# CapacitiveSensorBreakout-v1_0.net
KiCad netlist of a schematic drawn in EAGLE
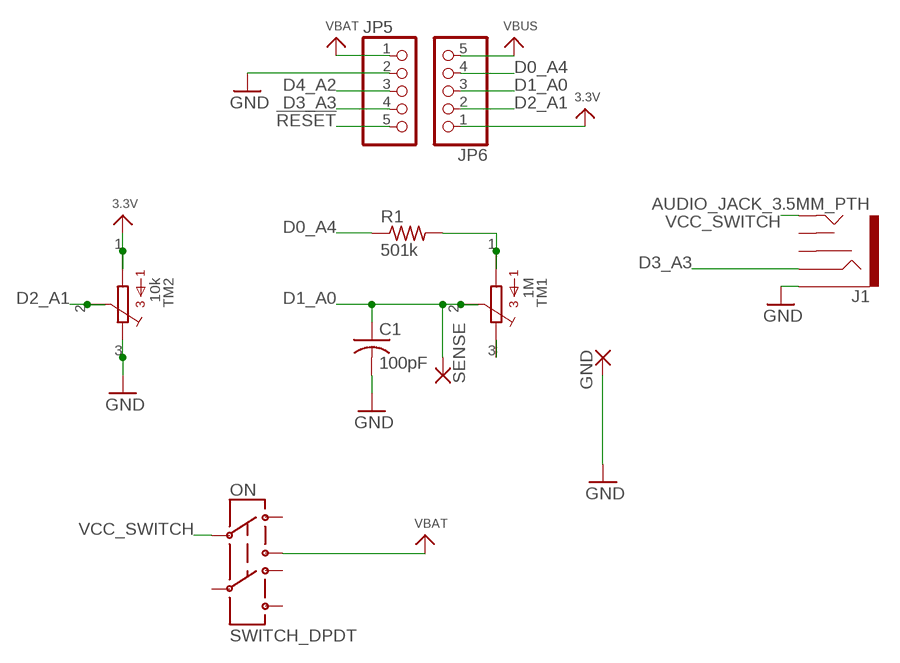
[diagram p0: schematic, sheet 1]

(export (version "E")
  (design (tool "Eeschema 10.0.6"))
  (components
    (comp (ref "C1")
      (value "100pF")
      (footprint "eagle-import:C0603")
      (libsource (lib "eagle-import") (part "C-USC0603"))
    )
    (comp (ref "GND")
      (value "1,6/0,8")
      (footprint "eagle-import:1,6_0,8")
      (libsource (lib "eagle-import") (part "1,6/0,8"))
    )
    (comp (ref "J1")
      (value "AUDIO_JACK_3.5MM_PTH")
      (footprint "eagle-import:AUDIO-JACK")
      (libsource (lib "eagle-import") (part "AUDIO_JACK_3.5MM_PTH"))
    )
    (comp (ref "JP5")
      (value "HEADER-1X576MIL")
      (footprint "eagle-import:1X05_ROUND_76")
      (libsource (lib "eagle-import") (part "HEADER-1X576MIL"))
    )
    (comp (ref "JP6")
      (value "HEADER-1X576MIL")
      (footprint "eagle-import:1X05_ROUND_76")
      (libsource (lib "eagle-import") (part "HEADER-1X576MIL"))
    )
    (comp (ref "ON")
      (value "SWITCH_DPDT")
      (footprint "eagle-import:JS_DPDT_TH")
      (libsource (lib "eagle-import") (part "SWITCH_DPDT"))
    )
    (comp (ref "R1")
      (value "501k")
      (footprint "eagle-import:R0603")
      (libsource (lib "eagle-import") (part "R-US_R0603"))
    )
    (comp (ref "SENSE")
      (value "1,6/0,8")
      (footprint "eagle-import:1,6_0,8")
      (libsource (lib "eagle-import") (part "1,6/0,8"))
    )
    (comp (ref "TM1")
      (value "1M")
      (footprint "eagle-import:3386-MULTI")
      (libsource (lib "eagle-import") (part "3386"))
    )
    (comp (ref "TM2")
      (value "10k")
      (footprint "eagle-import:3386-MULTI")
      (libsource (lib "eagle-import") (part "3386"))
    )
  )
  (nets
    (net (code "1") (name "/D0_A4") (class "Default")
      (node (ref "JP6") (pin "4") (pinfunction "4_4") (pintype "passive"))
      (node (ref "R1") (pin "1") (pinfunction "1_1") (pintype "passive"))
    )
    (net (code "2") (name "/D1_A0") (class "Default")
      (node (ref "C1") (pin "1") (pinfunction "1_1") (pintype "passive"))
      (node (ref "JP6") (pin "3") (pinfunction "3_3") (pintype "passive"))
      (node (ref "SENSE") (pin "1") (pinfunction "P_1") (pintype "passive"))
      (node (ref "TM1") (pin "2") (pinfunction "2_2") (pintype "passive"))
      (node (ref "TM1") (pin "5") (pinfunction "5_5") (pintype "passive"))
    )
    (net (code "3") (name "/D2_A1") (class "Default")
      (node (ref "JP6") (pin "2") (pinfunction "2_2") (pintype "passive"))
      (node (ref "TM2") (pin "2") (pinfunction "2_2") (pintype "passive"))
      (node (ref "TM2") (pin "5") (pinfunction "5_5") (pintype "passive"))
    )
    (net (code "4") (name "/D3_A3") (class "Default")
      (node (ref "J1") (pin "RING") (pinfunction "RING_RING") (pintype "bidirectional"))
      (node (ref "JP5") (pin "4") (pinfunction "4_4") (pintype "passive"))
    )
    (net (code "5") (name "/D4_A2") (class "Default")
      (node (ref "JP5") (pin "3") (pinfunction "3_3") (pintype "passive"))
    )
    (net (code "6") (name "/VCC_SWITCH") (class "Default")
      (node (ref "J1") (pin "TIP") (pinfunction "TIP_TIP") (pintype "bidirectional"))
      (node (ref "ON") (pin "2") (pinfunction "2_2") (pintype "bidirectional"))
    )
    (net (code "7") (name "/~{RESET}") (class "Default")
      (node (ref "JP5") (pin "5") (pinfunction "5_5") (pintype "passive"))
    )
    (net (code "8") (name "3.3V") (class "Default")
      (node (ref "JP6") (pin "1") (pinfunction "1_1") (pintype "passive"))
      (node (ref "TM2") (pin "1") (pinfunction "1_1") (pintype "passive"))
      (node (ref "TM2") (pin "4") (pinfunction "4_4") (pintype "passive"))
    )
    (net (code "9") (name "GND") (class "Default")
      (node (ref "C1") (pin "2") (pinfunction "2_2") (pintype "passive"))
      (node (ref "GND") (pin "1") (pinfunction "P_1") (pintype "passive"))
      (node (ref "J1") (pin "SLEEVE") (pinfunction "SLEEVE_SLEEVE") (pintype "bidirectional"))
      (node (ref "JP5") (pin "2") (pinfunction "2_2") (pintype "passive"))
      (node (ref "TM2") (pin "3") (pinfunction "3_3") (pintype "passive"))
      (node (ref "TM2") (pin "6") (pinfunction "6_6") (pintype "passive"))
    )
    (net (code "10") (name "Net-(R1-Pad2)") (class "Default")
      (node (ref "R1") (pin "2") (pinfunction "2_2") (pintype "passive"))
      (node (ref "TM1") (pin "1") (pinfunction "1_1") (pintype "passive"))
      (node (ref "TM1") (pin "4") (pinfunction "4_4") (pintype "passive"))
    )
    (net (code "11") (name "Net-(TM1-Pad3)") (class "Default")
      (node (ref "TM1") (pin "3") (pinfunction "3_3") (pintype "passive"))
      (node (ref "TM1") (pin "6") (pinfunction "6_6") (pintype "passive"))
    )
    (net (code "12") (name "VBAT") (class "Default")
      (node (ref "JP5") (pin "1") (pinfunction "1_1") (pintype "passive"))
      (node (ref "ON") (pin "3") (pinfunction "3_3") (pintype "bidirectional"))
    )
    (net (code "13") (name "VBUS") (class "Default")
      (node (ref "JP6") (pin "5") (pinfunction "5_5") (pintype "passive"))
    )
    (net (code "14") (name "unconnected-(J1-PadRSH)") (class "Default")
      (node (ref "J1") (pin "RSH") (pinfunction "RSH_RSH") (pintype "bidirectional"))
    )
    (net (code "15") (name "unconnected-(J1-PadTSH)") (class "Default")
      (node (ref "J1") (pin "TSH") (pinfunction "TSH_TSH") (pintype "bidirectional"))
    )
    (net (code "16") (name "unconnected-(ON-Pad1)") (class "Default")
      (node (ref "ON") (pin "1") (pinfunction "1_1") (pintype "bidirectional"))
    )
    (net (code "17") (name "unconnected-(ON-Pad4)") (class "Default")
      (node (ref "ON") (pin "4") (pinfunction "4_4") (pintype "bidirectional"))
    )
    (net (code "18") (name "unconnected-(ON-Pad5)") (class "Default")
      (node (ref "ON") (pin "5") (pinfunction "5_5") (pintype "bidirectional"))
    )
    (net (code "19") (name "unconnected-(ON-Pad6)") (class "Default")
      (node (ref "ON") (pin "6") (pinfunction "6_6") (pintype "bidirectional"))
    )
  )
)
